# 22_-_SD_CARD.net
KiCad netlist of a schematic drawn in Altium Designer
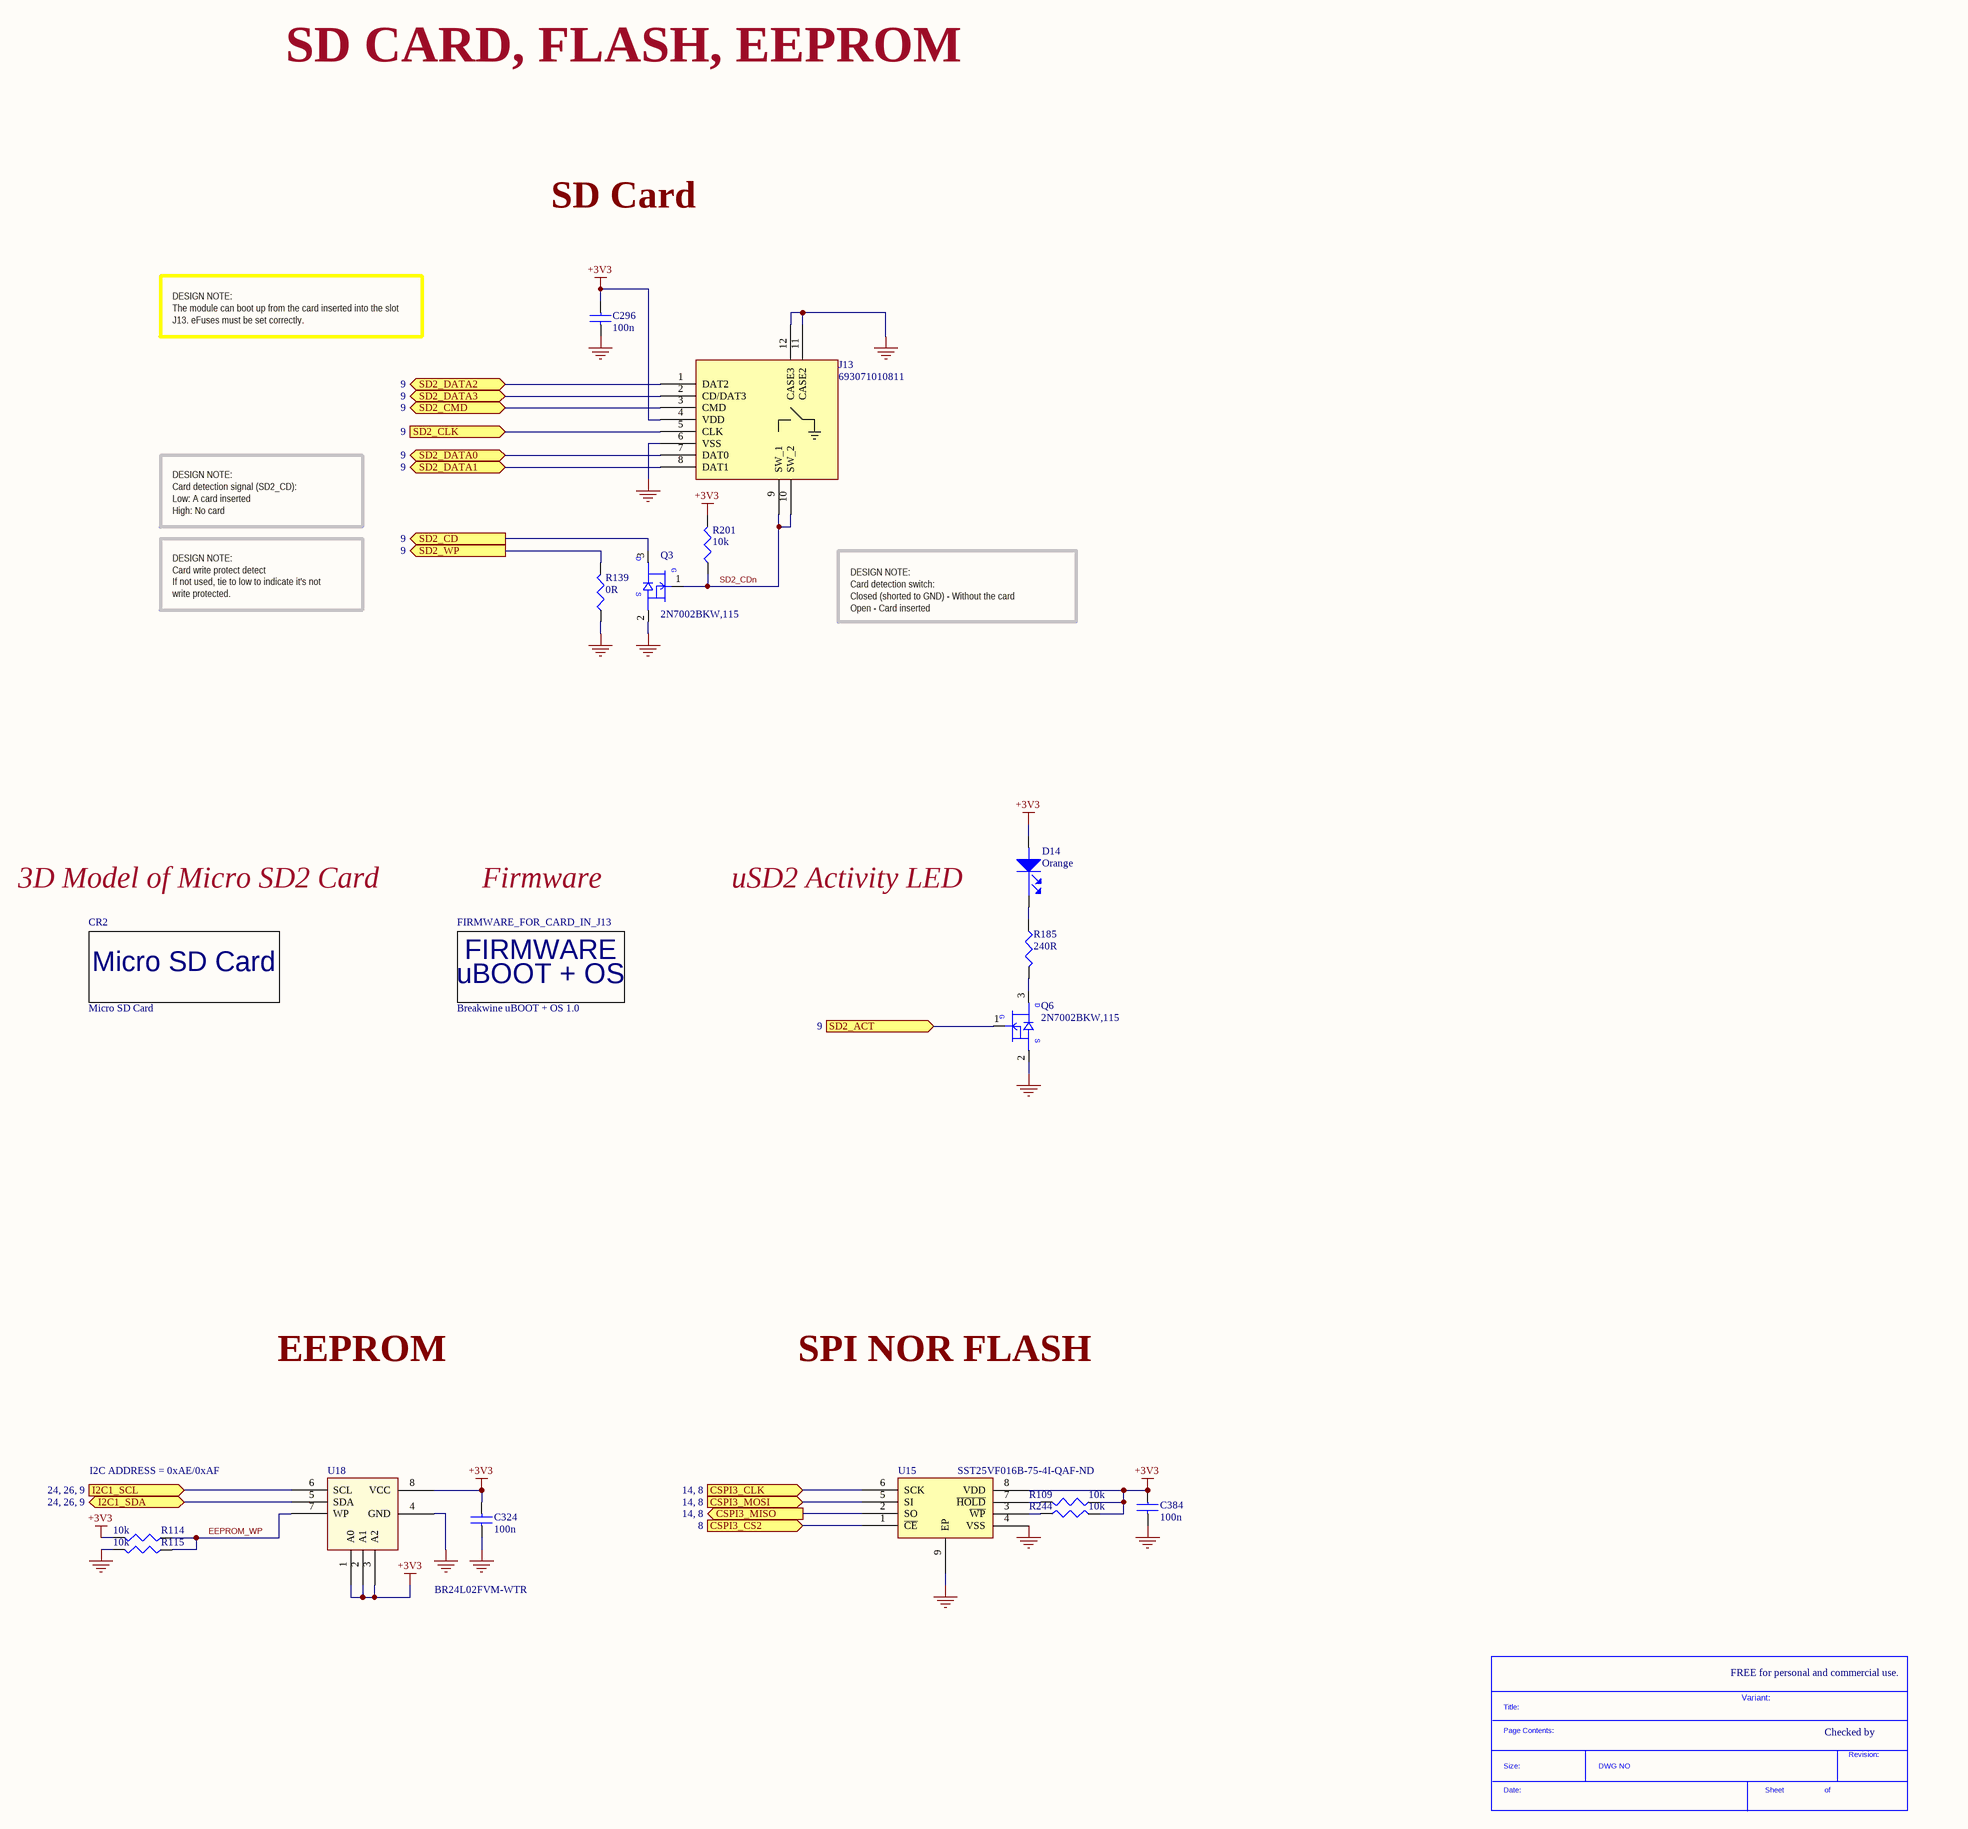
[diagram p0: [22] - SD CARD.SchDoc]

(export (version "E")
  (design (tool "Eeschema 10.0.6"))
  (components
    (comp (ref "*") (value "SDTitleBlock") (libsource (lib "*") (part "SDTitleBlock")))
    (comp (ref "C296")
      (value "100n")
      (footprint "C0402")
      (description "CAP CER .10UF 50V X5R 10% 0402")
      (fields
        (field (name "MANUFACTURER") "TDK Corporation")
        (field (name "MANUFACTURER PART NUMBER") "C1005X5R1H104K")
      )
      (libsource (lib "Integrated_Library_FEDEVEL_APR_2015") (part "C1005X5R1H104K"))
    )
    (comp (ref "C324")
      (value "100n")
      (footprint "C0402")
      (description "CAP CER .10UF 50V X5R 10% 0402")
      (fields
        (field (name "MANUFACTURER") "TDK Corporation")
        (field (name "MANUFACTURER PART NUMBER") "C1005X5R1H104K")
      )
      (libsource (lib "Integrated_Library_FEDEVEL_APR_2015") (part "C1005X5R1H104K"))
    )
    (comp (ref "C384")
      (value "100n")
      (footprint "C0402")
      (description "CAP CER .10UF 50V X5R 10% 0402")
      (fields
        (field (name "MANUFACTURER") "TDK Corporation")
        (field (name "MANUFACTURER PART NUMBER") "C1005X5R1H104K")
      )
      (libsource (lib "Integrated_Library_FEDEVEL_APR_2015") (part "C1005X5R1H104K"))
    )
    (comp (ref "CR2")
      (value "Micro SD Card")
      (footprint "Micro_SD_card")
      (description "Card Micro SD")
      (fields (field (name ".CREATOR") "MM"))
      (libsource (lib "Integrated_Library_FEDEVEL_APR_2015") (part "Card_Micro_SD"))
    )
    (comp (ref "D14")
      (value "Orange")
      (footprint "LED_0603")
      (description "LED SMARTLED ORANGE 606NM 0603")
      (fields
        (field (name "MANUFACTURER") "OSRAM Opto Semiconductors Inc")
        (field (name "MANUFACTURER PART NUMBER") "LO L29K-H2K1-24-Z")
      )
      (libsource (lib "Integrated_Library_FEDEVEL_APR_2015") (part "LO L29K-H2K1-24-Z"))
    )
    (comp (ref "FIRMWARE_FOR_CARD_IN_J13")
      (value "Breakwine uBOOT + OS 1.0")
      (fields (field (name ".CREATOR") "MM"))
      (libsource (lib "Integrated_Library_FEDEVEL_APR_2015") (part "FIRMWARE_Breakwine_uBOOT_OS 1.0"))
    )
    (comp (ref "J13")
      (value "693071010811")
      (footprint "693071010811")
      (description "CONN MICRO SD 8 POS SMD")
      (fields (field (name "MANUFACTURER") "Wurth Electronics Inc") (field (name ".CREATOR") "MM"))
      (libsource (lib "Integrated_Library_FEDEVEL_APR_2015") (part "693071010811"))
    )
    (comp (ref "Q3")
      (value "2N7002BKW,115")
      (footprint "SC70_SOT323")
      (description "MOSFET N-CH 60V 310MA SOT323")
      (fields (field (name "MANUFACTURER") "NXP Semiconductors"))
      (libsource (lib "Integrated_Library_FEDEVEL_APR_2015") (part "2N7002BKW,115"))
    )
    (comp (ref "Q6")
      (value "2N7002BKW,115")
      (footprint "SC70_SOT323")
      (description "MOSFET N-CH 60V 310MA SOT323")
      (fields (field (name "MANUFACTURER") "NXP Semiconductors"))
      (libsource (lib "Integrated_Library_FEDEVEL_APR_2015") (part "2N7002BKW,115"))
    )
    (comp (ref "R109")
      (value "10k")
      (footprint "R0402")
      (description "RES 10.0K OHM 1/16W 1% 0402 SMD")
      (fields
        (field (name "MANUFACTURER") "Yageo")
        (field (name "MANUFACTURER PART NUMBER") "RC0402FR-0710KL")
      )
      (libsource (lib "Integrated_Library_FEDEVEL_APR_2015") (part "RC0402FR-0710KL"))
    )
    (comp (ref "R114")
      (value "10k")
      (footprint "R0402")
      (description "RES 10.0K OHM 1/16W 1% 0402 SMD")
      (fields
        (field (name "MANUFACTURER") "Yageo")
        (field (name "MANUFACTURER PART NUMBER") "RC0402FR-0710KL")
      )
      (libsource (lib "Integrated_Library_FEDEVEL_APR_2015") (part "RC0402FR-0710KL"))
    )
    (comp (ref "R115")
      (value "10k")
      (footprint "R0402")
      (description "RES 10.0K OHM 1/16W 1% 0402 SMD")
      (fields
        (field (name "MANUFACTURER") "Yageo")
        (field (name "MANUFACTURER PART NUMBER") "RC0402FR-0710KL")
      )
      (libsource (lib "Integrated_Library_FEDEVEL_APR_2015") (part "RC0402FR-0710KL"))
    )
    (comp (ref "R139")
      (value "0R")
      (footprint "R0402")
      (description "RES 0.0 OHM 1/16W 0402 SMD")
      (fields
        (field (name "MANUFACTURER") "Yageo")
        (field (name "MANUFACTURER PART NUMBER") "RC0402JR-070RL")
      )
      (libsource (lib "Integrated_Library_FEDEVEL_APR_2015") (part "RC0402JR-070RL"))
    )
    (comp (ref "R185")
      (value "240R")
      (footprint "R0402")
      (description "RES TF 240 OHM 1% 0.0625W 0402")
      (fields
        (field (name "MANUFACTURER") "Stackpole Electronics Inc")
        (field (name "MANUFACTURER PART NUMBER") "RMCF0402FT240R")
      )
      (libsource (lib "Integrated_Library_FEDEVEL_APR_2015") (part "RMCF0402FT240R"))
    )
    (comp (ref "R201")
      (value "10k")
      (footprint "R0402")
      (description "RES 10.0K OHM 1/16W 1% 0402 SMD")
      (fields
        (field (name "MANUFACTURER") "Yageo")
        (field (name "MANUFACTURER PART NUMBER") "RC0402FR-0710KL")
      )
      (libsource (lib "Integrated_Library_FEDEVEL_APR_2015") (part "RC0402FR-0710KL"))
    )
    (comp (ref "R244")
      (value "10k")
      (footprint "R0402")
      (description "RES 10.0K OHM 1/16W 1% 0402 SMD")
      (fields
        (field (name "MANUFACTURER") "Yageo")
        (field (name "MANUFACTURER PART NUMBER") "RC0402FR-0710KL")
      )
      (libsource (lib "Integrated_Library_FEDEVEL_APR_2015") (part "RC0402FR-0710KL"))
    )
    (comp (ref "U15")
      (value "SST25VF016B-75-4I-QAF-ND")
      (footprint "WSON8_6X5MM")
      (description "IC FLASH 16MBIT 75MHZ 8WSON")
      (fields
        (field (name "MANUFACTURER") "Microchip Technology")
        (field (name "MANUFACTURER PART NUMBER") "SST25VF016B-75-4I-QAF")
        (field (name ".CREATOR") "MM")
      )
      (libsource (lib "Integrated_Library_FEDEVEL_APR_2015") (part "SST25VF016B-75-4I-QAF"))
    )
    (comp (ref "U18")
      (value "BR24L02FVM-WTR")
      (footprint "MSOP8 _SMALLER")
      (description "IC EEPROM 2KBIT 400KHZ 8MSOP")
      (fields (field (name "MANUFACTURER") "Rohm Semiconductor"))
      (libsource (lib "Integrated_Library_FEDEVEL_APR_2015") (part "BR24L02FVM-WTR"))
    )
  )
  (nets
    (net (code "1") (name "+3V3") (class "Default")
      (node (ref "C296") (pin "1") (pinfunction "1_1") (pintype "passive"))
      (node (ref "C324") (pin "2") (pinfunction "2_2") (pintype "passive"))
      (node (ref "C384") (pin "1") (pinfunction "1_1") (pintype "passive"))
      (node (ref "D14") (pin "2") (pinfunction "ANODE_2") (pintype "passive"))
      (node (ref "J13") (pin "4") (pinfunction "VDD_4") (pintype "passive"))
      (node (ref "R109") (pin "1") (pinfunction "1_1") (pintype "passive"))
      (node (ref "R114") (pin "2") (pinfunction "2_2") (pintype "passive"))
      (node (ref "R201") (pin "2") (pinfunction "2_2") (pintype "passive"))
      (node (ref "R244") (pin "2") (pinfunction "2_2") (pintype "passive"))
      (node (ref "U15") (pin "8") (pinfunction "VDD_8") (pintype "passive"))
      (node (ref "U18") (pin "1") (pinfunction "A0_1") (pintype "passive"))
      (node (ref "U18") (pin "2") (pinfunction "A1_2") (pintype "passive"))
      (node (ref "U18") (pin "3") (pinfunction "A2_3") (pintype "passive"))
      (node (ref "U18") (pin "8") (pinfunction "VCC_8") (pintype "power_in"))
    )
    (net (code "2") (name "/CSPI3_CLK") (class "Default")
      (node (ref "U15") (pin "6") (pinfunction "SCK_6") (pintype "passive"))
    )
    (net (code "3") (name "/CSPI3_CS2") (class "Default")
      (node (ref "U15") (pin "1") (pinfunction "~{CE}_1") (pintype "passive"))
    )
    (net (code "4") (name "/CSPI3_MISO") (class "Default")
      (node (ref "U15") (pin "2") (pinfunction "SO_2") (pintype "passive"))
    )
    (net (code "5") (name "/CSPI3_MOSI") (class "Default")
      (node (ref "U15") (pin "5") (pinfunction "SI_5") (pintype "passive"))
    )
    (net (code "6") (name "/EEPROM_WP") (class "Default")
      (node (ref "R114") (pin "1") (pinfunction "1_1") (pintype "passive"))
      (node (ref "R115") (pin "1") (pinfunction "1_1") (pintype "passive"))
      (node (ref "U18") (pin "7") (pinfunction "WP_7") (pintype "passive"))
    )
    (net (code "7") (name "/I2C1_SCL") (class "Default")
      (node (ref "U18") (pin "6") (pinfunction "SCL_6") (pintype "passive"))
    )
    (net (code "8") (name "/I2C1_SDA") (class "Default")
      (node (ref "U18") (pin "5") (pinfunction "SDA_5") (pintype "passive"))
    )
    (net (code "9") (name "/SD2_ACT") (class "Default")
      (node (ref "Q6") (pin "1") (pinfunction "GATE_1") (pintype "passive"))
    )
    (net (code "10") (name "/SD2_CD") (class "Default")
      (node (ref "Q3") (pin "3") (pinfunction "DRAIN_3") (pintype "passive"))
    )
    (net (code "11") (name "/SD2_CDn") (class "Default")
      (node (ref "J13") (pin "10") (pinfunction "SW_2_10") (pintype "passive"))
      (node (ref "J13") (pin "9") (pinfunction "SW_1_9") (pintype "passive"))
      (node (ref "Q3") (pin "1") (pinfunction "GATE_1") (pintype "passive"))
      (node (ref "R201") (pin "1") (pinfunction "1_1") (pintype "passive"))
    )
    (net (code "12") (name "/SD2_CLK") (class "Default")
      (node (ref "J13") (pin "5") (pinfunction "CLK_5") (pintype "passive"))
    )
    (net (code "13") (name "/SD2_CMD") (class "Default")
      (node (ref "J13") (pin "3") (pinfunction "CMD_3") (pintype "passive"))
    )
    (net (code "14") (name "/SD2_DATA0") (class "Default")
      (node (ref "J13") (pin "7") (pinfunction "DAT0_7") (pintype "passive"))
    )
    (net (code "15") (name "/SD2_DATA1") (class "Default")
      (node (ref "J13") (pin "8") (pinfunction "DAT1_8") (pintype "passive"))
    )
    (net (code "16") (name "/SD2_DATA2") (class "Default")
      (node (ref "J13") (pin "1") (pinfunction "DAT2_1") (pintype "passive"))
    )
    (net (code "17") (name "/SD2_DATA3") (class "Default")
      (node (ref "J13") (pin "2") (pinfunction "CD/DAT3_2") (pintype "passive"))
    )
    (net (code "18") (name "/SD2_WP") (class "Default")
      (node (ref "R139") (pin "2") (pinfunction "2_2") (pintype "passive"))
    )
    (net (code "19") (name "GND") (class "Default")
      (node (ref "C296") (pin "2") (pinfunction "2_2") (pintype "passive"))
      (node (ref "C324") (pin "1") (pinfunction "1_1") (pintype "passive"))
      (node (ref "C384") (pin "2") (pinfunction "2_2") (pintype "passive"))
      (node (ref "J13") (pin "11") (pinfunction "CASE2_11") (pintype "passive"))
      (node (ref "J13") (pin "12") (pinfunction "CASE3_12") (pintype "passive"))
      (node (ref "J13") (pin "6") (pinfunction "VSS_6") (pintype "passive"))
      (node (ref "Q3") (pin "2") (pinfunction "SOURCE_2") (pintype "passive"))
      (node (ref "Q6") (pin "2") (pinfunction "SOURCE_2") (pintype "passive"))
      (node (ref "R115") (pin "2") (pinfunction "2_2") (pintype "passive"))
      (node (ref "R139") (pin "1") (pinfunction "1_1") (pintype "passive"))
      (node (ref "U15") (pin "4") (pinfunction "VSS_4") (pintype "passive"))
      (node (ref "U15") (pin "9") (pinfunction "EP_9") (pintype "passive"))
      (node (ref "U18") (pin "4") (pinfunction "GND_4") (pintype "power_in"))
    )
    (net (code "20") (name "Net-(D14-cathode)") (class "Default")
      (node (ref "D14") (pin "1") (pinfunction "cathode_1") (pintype "passive"))
      (node (ref "R185") (pin "1") (pinfunction "1_1") (pintype "passive"))
    )
    (net (code "21") (name "Net-(Q6-DRAIN)") (class "Default")
      (node (ref "Q6") (pin "3") (pinfunction "DRAIN_3") (pintype "passive"))
      (node (ref "R185") (pin "2") (pinfunction "2_2") (pintype "passive"))
    )
    (net (code "22") (name "Net-(U15-~{HOLD})") (class "Default")
      (node (ref "R109") (pin "2") (pinfunction "2_2") (pintype "passive"))
      (node (ref "U15") (pin "7") (pinfunction "~{HOLD}_7") (pintype "passive"))
    )
    (net (code "23") (name "Net-(U15-~{WP})") (class "Default")
      (node (ref "R244") (pin "1") (pinfunction "1_1") (pintype "passive"))
      (node (ref "U15") (pin "3") (pinfunction "~{WP}_3") (pintype "passive"))
    )
  )
)
